# main.net
KiCad netlist of a schematic drawn in EAGLE
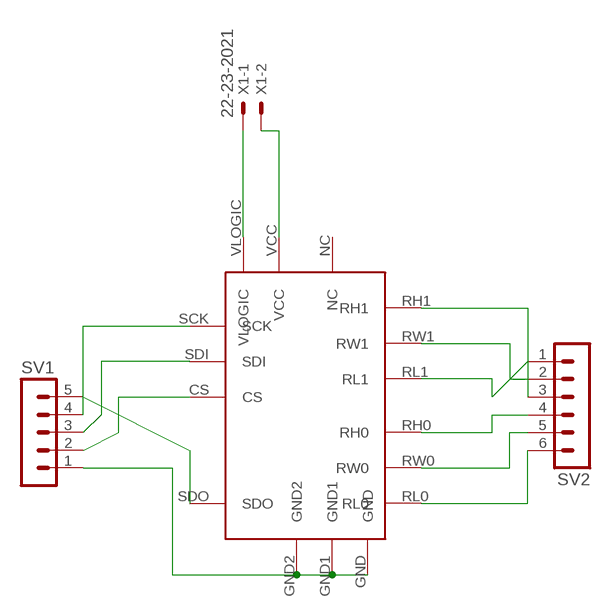
[diagram p0: schematic, sheet 1]

(export (version "E")
  (design (tool "Eeschema 10.0.6"))
  (components
    (comp (ref "SV1")
      (value "MA05-1")
      (footprint "eagle-import:MA05-1")
      (libsource (lib "eagle-import") (part "MA05-1"))
    )
    (comp (ref "SV2")
      (value "MA06-1")
      (footprint "eagle-import:MA06-1")
      (libsource (lib "eagle-import") (part "MA06-1"))
    )
    (comp (ref "U$1")
      (value "ISL23428")
      (footprint "eagle-import:UTQFN16")
      (libsource (lib "eagle-import") (part "ISL23428"))
    )
    (comp (ref "X1")
      (value "22-23-2021")
      (footprint "eagle-import:22-23-2021")
      (fields (field (name "MF") "MOLEX"))
      (libsource (lib "eagle-import") (part "22-23-2021"))
    )
  )
  (nets
    (net (code "1") (name "Net-(SV1-Pad1)") (class "Default")
      (node (ref "SV1") (pin "1") (pinfunction "1_1") (pintype "passive"))
      (node (ref "U$1") (pin "GND") (pinfunction "GND_GND") (pintype "bidirectional"))
      (node (ref "U$1") (pin "GND1") (pinfunction "GND1_GND1") (pintype "bidirectional"))
      (node (ref "U$1") (pin "GND2") (pinfunction "GND2_GND2") (pintype "bidirectional"))
    )
    (net (code "2") (name "Net-(SV1-Pad2)") (class "Default")
      (node (ref "SV1") (pin "2") (pinfunction "2_2") (pintype "passive"))
      (node (ref "U$1") (pin "CS") (pinfunction "CS_CS") (pintype "bidirectional"))
    )
    (net (code "3") (name "Net-(SV1-Pad3)") (class "Default")
      (node (ref "SV1") (pin "3") (pinfunction "3_3") (pintype "passive"))
      (node (ref "U$1") (pin "SDI") (pinfunction "SDI_SDI") (pintype "bidirectional"))
    )
    (net (code "4") (name "Net-(SV1-Pad4)") (class "Default")
      (node (ref "SV1") (pin "4") (pinfunction "4_4") (pintype "passive"))
      (node (ref "U$1") (pin "SCK") (pinfunction "SCK_SCK") (pintype "bidirectional"))
    )
    (net (code "5") (name "Net-(SV1-Pad5)") (class "Default")
      (node (ref "SV1") (pin "5") (pinfunction "5_5") (pintype "passive"))
      (node (ref "U$1") (pin "SDO") (pinfunction "SDO_SDO") (pintype "bidirectional"))
    )
    (net (code "6") (name "Net-(SV2-Pad1)") (class "Default")
      (node (ref "SV2") (pin "1") (pinfunction "1_1") (pintype "passive"))
      (node (ref "U$1") (pin "RL1") (pinfunction "RL1_RL1") (pintype "bidirectional"))
    )
    (net (code "7") (name "Net-(SV2-Pad2)") (class "Default")
      (node (ref "SV2") (pin "2") (pinfunction "2_2") (pintype "passive"))
      (node (ref "U$1") (pin "RW1") (pinfunction "RW1_RW1") (pintype "bidirectional"))
    )
    (net (code "8") (name "Net-(SV2-Pad3)") (class "Default")
      (node (ref "SV2") (pin "3") (pinfunction "3_3") (pintype "passive"))
      (node (ref "U$1") (pin "RH1") (pinfunction "RH1_RH1") (pintype "bidirectional"))
    )
    (net (code "9") (name "Net-(SV2-Pad4)") (class "Default")
      (node (ref "SV2") (pin "4") (pinfunction "4_4") (pintype "passive"))
      (node (ref "U$1") (pin "RH0") (pinfunction "RH0_RH0") (pintype "bidirectional"))
    )
    (net (code "10") (name "Net-(SV2-Pad5)") (class "Default")
      (node (ref "SV2") (pin "5") (pinfunction "5_5") (pintype "passive"))
      (node (ref "U$1") (pin "RW0") (pinfunction "RW0_RW0") (pintype "bidirectional"))
    )
    (net (code "11") (name "Net-(SV2-Pad6)") (class "Default")
      (node (ref "SV2") (pin "6") (pinfunction "6_6") (pintype "passive"))
      (node (ref "U$1") (pin "RL0") (pinfunction "RL0_RL0") (pintype "bidirectional"))
    )
    (net (code "12") (name "Net-(X1A-S)") (class "Default")
      (node (ref "U$1") (pin "VLOGIC") (pinfunction "VLOGIC_VLOGIC") (pintype "bidirectional"))
      (node (ref "X1") (pin "1") (pinfunction "S_1") (pintype "passive"))
    )
    (net (code "13") (name "Net-(X1B-S)") (class "Default")
      (node (ref "U$1") (pin "VCC") (pinfunction "VCC_VCC") (pintype "bidirectional"))
      (node (ref "X1") (pin "2") (pinfunction "S_2") (pintype "passive"))
    )
    (net (code "14") (name "unconnected-(U$1-PadNC)") (class "Default")
      (node (ref "U$1") (pin "NC") (pinfunction "NC_NC") (pintype "bidirectional"))
    )
  )
)
